# Isolated-5V-5V.net
KiCad netlist of a schematic drawn in Altium Designer
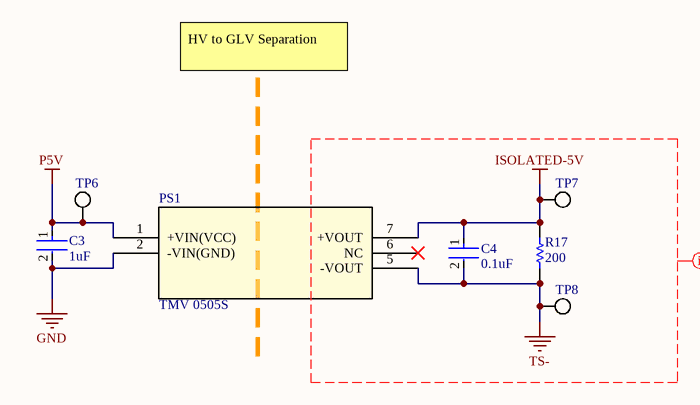
[diagram p0: Isolated-5V-5V.SchDoc]

(export (version "E")
  (design (tool "Eeschema 10.0.6"))
  (components
    (comp (ref "C3")
      (value "1uF")
      (footprint "FP-C3216-160-0_2-IPC_B")
      (description "Multilayer Ceramic Capacitors 1uF ±10% 50V X7R SMD 1206")
      (fields (field (name "VOLTAGE") "25V") (field (name "TOLERANCE") "10%"))
      (libsource (lib "Altium Content Vault") (part "11868f565c42a9108669ba33697ecf6"))
    )
    (comp (ref "C4")
      (value "0.1uF")
      (footprint "FP-C1206C-EB-MFG")
      (description "CAP CER 0.1UF 250V X7R 1206")
      (fields
        (field (name "MANUFACTURER PART NUMBER") "C1206C104KARACTU")
        (field (name "MANUFACTURER") "KEMET")
      )
      (libsource (lib "Altium Content Vault") (part "b4654b650e69147ec39a6b967a45e02"))
    )
    (comp (ref "PS1")
      (value "TMV 0505S")
      (footprint "TMV05-SINGLE_TRP")
      (description "No Description Available")
      (fields (field (name "COPYRIGHT") "Copyright (C) 2018 Accelerated Designs. All rights reserved"))
      (libsource (lib "University of California Riverside - FSAE") (part "TMV 0505S"))
    )
    (comp (ref "R17")
      (value "200")
      (footprint "RESC3216X70X50LL05T20")
      (fields (field (name "PART NUMBER") "ERJ-8ENF2000V") (field (name "MANUFACTURER") "Panasonic"))
      (libsource (lib "Altium Content Vault") (part "RES"))
    )
    (comp (ref "TP6")
      (value "~")
      (footprint "FOOTPRINT-GENERIC-TP-VIA-1MM")
      (libsource (lib "University of California Riverside - FSAE") (part "Misc-Generic-TP"))
    )
    (comp (ref "TP7")
      (value "~")
      (footprint "FOOTPRINT-GENERIC-TP-VIA-1MM")
      (libsource (lib "University of California Riverside - FSAE") (part "Misc-Generic-TP"))
    )
    (comp (ref "TP8")
      (value "~")
      (footprint "FOOTPRINT-GENERIC-TP-VIA-1MM")
      (libsource (lib "University of California Riverside - FSAE") (part "Misc-Generic-TP"))
    )
  )
  (nets
    (net (code "1") (name "GND") (class "Default")
      (node (ref "C3") (pin "2") (pinfunction "2_2") (pintype "passive"))
      (node (ref "PS1") (pin "2") (pinfunction "-VIN(GND)_2") (pintype "passive"))
    )
    (net (code "2") (name "ISOLATED-5V") (class "Default")
      (node (ref "C4") (pin "1") (pinfunction "1_1") (pintype "passive"))
      (node (ref "PS1") (pin "7") (pinfunction "+VOUT_7") (pintype "power_in"))
      (node (ref "R17") (pin "2") (pinfunction "2_2") (pintype "passive"))
      (node (ref "TP7") (pin "1") (pinfunction "TP_1") (pintype "passive"))
    )
    (net (code "3") (name "P5V") (class "Default")
      (node (ref "C3") (pin "1") (pinfunction "1_1") (pintype "passive"))
      (node (ref "PS1") (pin "1") (pinfunction "+VIN(VCC)_1") (pintype "power_in"))
      (node (ref "TP6") (pin "1") (pinfunction "TP_1") (pintype "passive"))
    )
    (net (code "4") (name "TS-") (class "Default")
      (node (ref "C4") (pin "2") (pinfunction "2_2") (pintype "passive"))
      (node (ref "PS1") (pin "5") (pinfunction "-VOUT_5") (pintype "power_in"))
      (node (ref "R17") (pin "1") (pinfunction "1_1") (pintype "passive"))
      (node (ref "TP8") (pin "1") (pinfunction "TP_1") (pintype "passive"))
    )
    (net (code "5") (name "unconnected-(PS1-NC-Pad6)") (class "Default")
      (node (ref "PS1") (pin "6") (pinfunction "NC_6") (pintype "passive+no_connect"))
    )
  )
)
